# CPU.net
KiCad netlist of a schematic drawn in Altium Designer
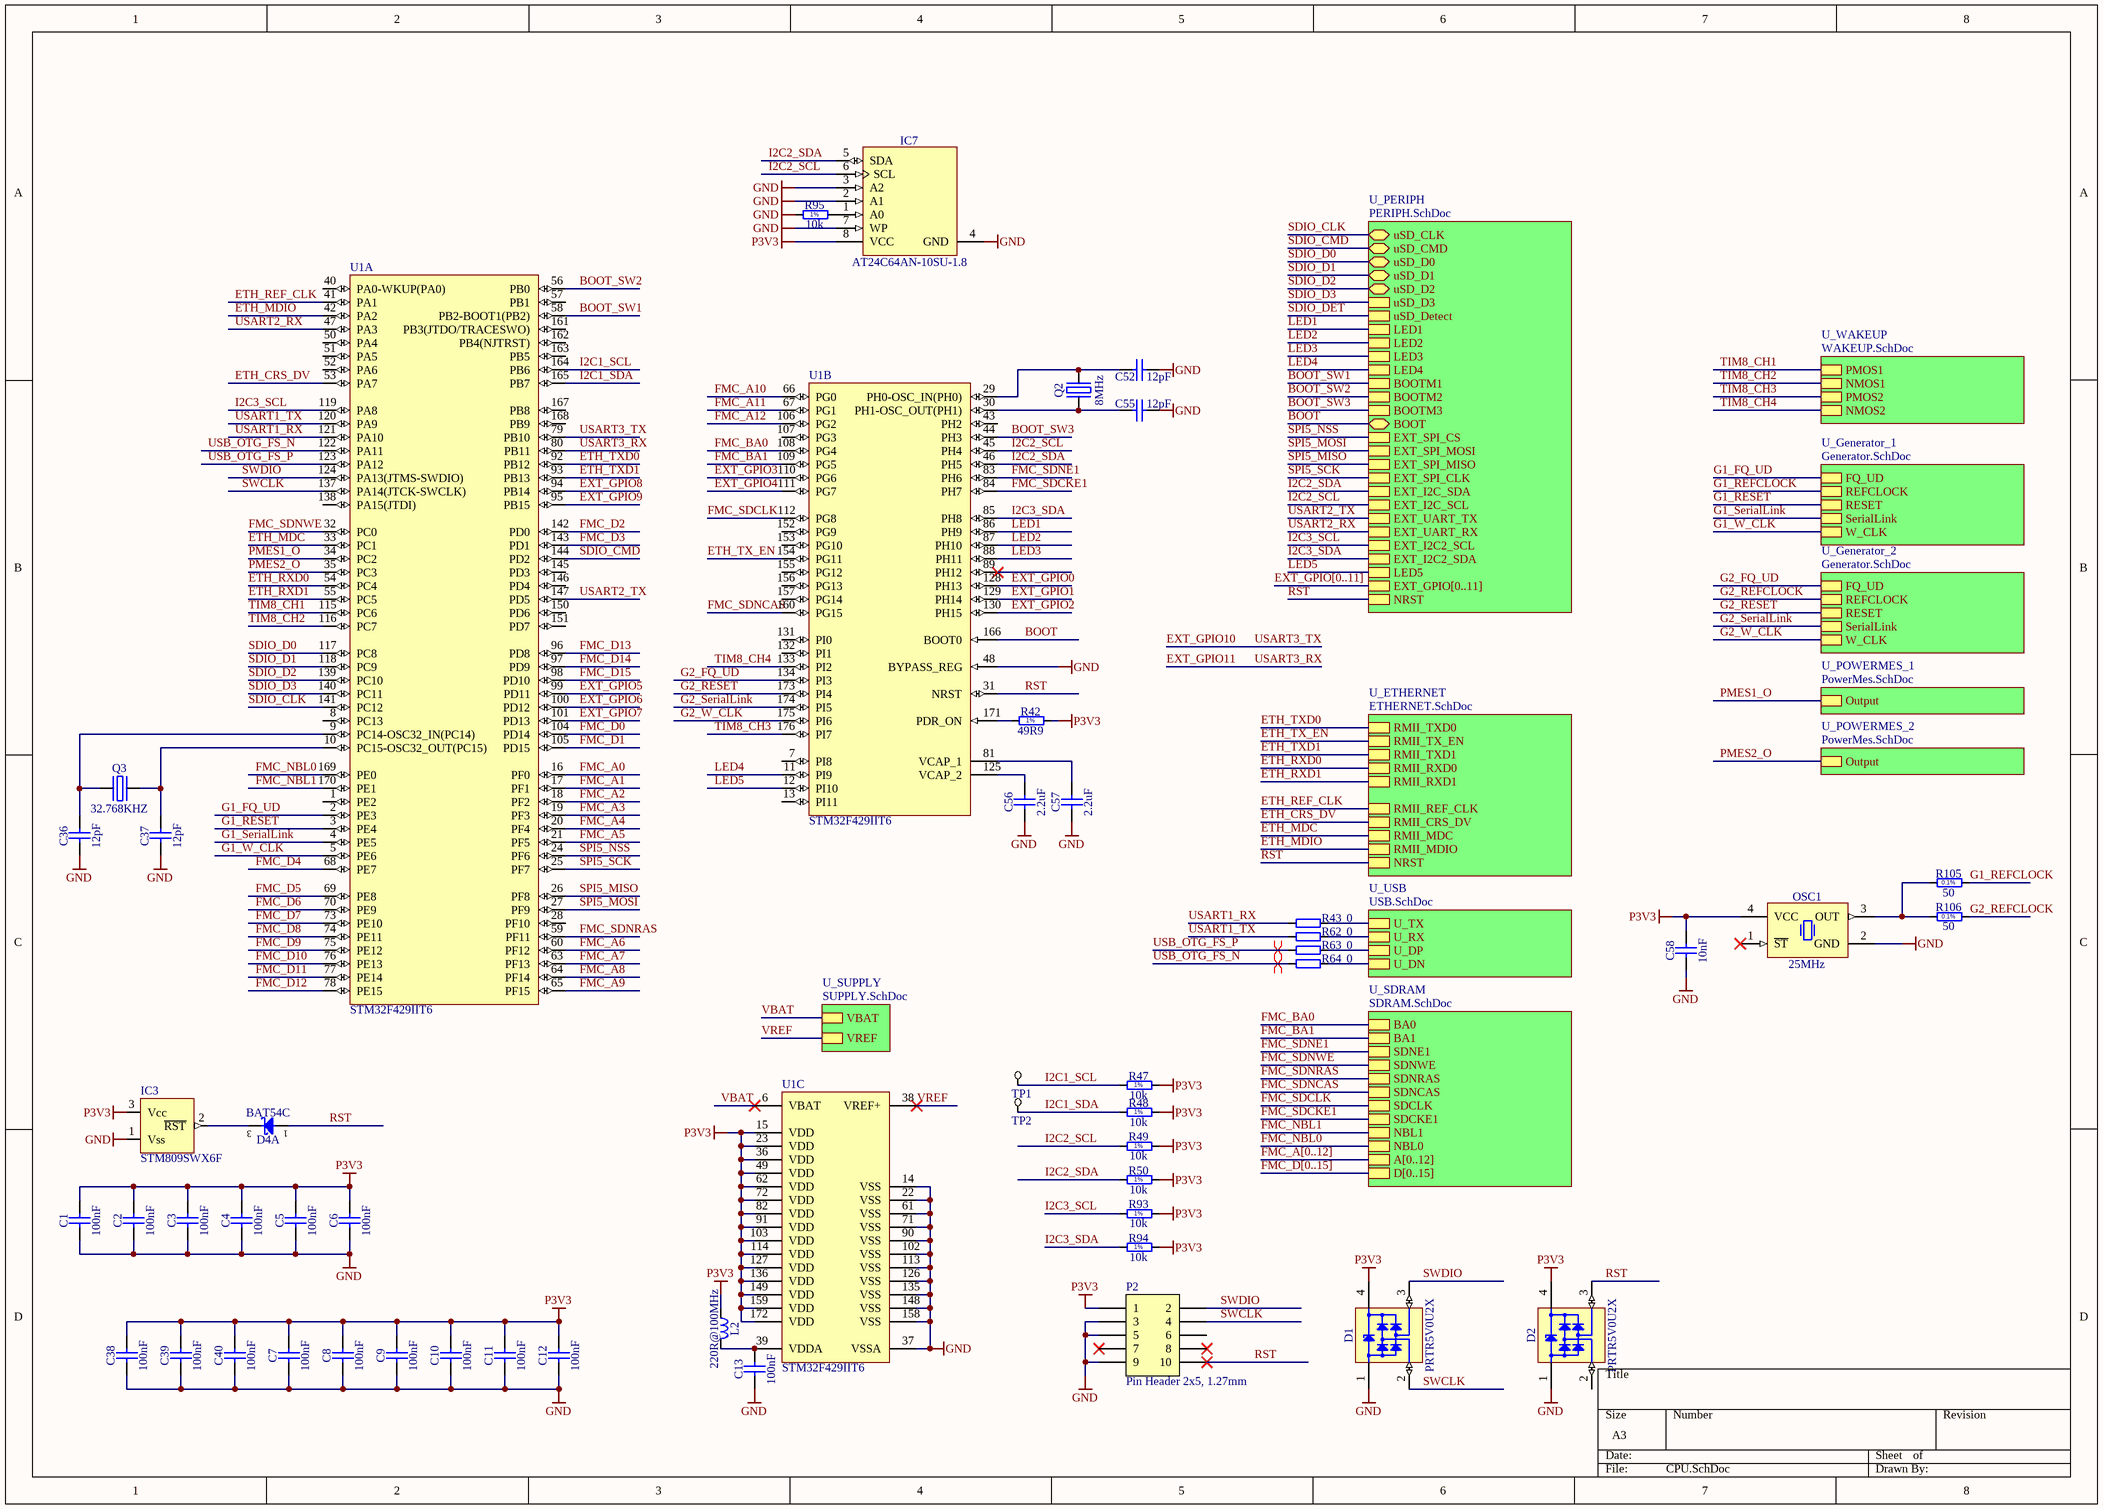
[diagram p0: CPU.SchDoc]

(export (version "E")
  (design (tool "Eeschema 10.0.6"))
  (components
    (comp (ref "C1")
      (value "100nF")
      (footprint "CAPC1005X55N")
      (description "Non-polarised capacitor")
      (fields
        (field (name "PART NUMBER") "CC0402_100NF_16V_10%_X5R")
        (field (name "VOLTAGE") "16V")
        (field (name "AUTHOR") "CERN DEM JLC")
      )
      (libsource (lib "Capacitors") (part "Capacitor - non polarized"))
    )
    (comp (ref "C2")
      (value "100nF")
      (footprint "CAPC1005X55N")
      (description "Non-polarised capacitor")
      (fields
        (field (name "PART NUMBER") "CC0402_100NF_16V_10%_X5R")
        (field (name "VOLTAGE") "16V")
        (field (name "AUTHOR") "CERN DEM JLC")
      )
      (libsource (lib "Capacitors") (part "Capacitor - non polarized"))
    )
    (comp (ref "C3")
      (value "100nF")
      (footprint "CAPC1005X55N")
      (description "Non-polarised capacitor")
      (fields
        (field (name "PART NUMBER") "CC0402_100NF_16V_10%_X5R")
        (field (name "VOLTAGE") "16V")
        (field (name "AUTHOR") "CERN DEM JLC")
      )
      (libsource (lib "Capacitors") (part "Capacitor - non polarized"))
    )
    (comp (ref "C4")
      (value "100nF")
      (footprint "CAPC1005X55N")
      (description "Non-polarised capacitor")
      (fields
        (field (name "PART NUMBER") "CC0402_100NF_16V_10%_X5R")
        (field (name "VOLTAGE") "16V")
        (field (name "AUTHOR") "CERN DEM JLC")
      )
      (libsource (lib "Capacitors") (part "Capacitor - non polarized"))
    )
    (comp (ref "C5")
      (value "100nF")
      (footprint "CAPC1005X55N")
      (description "Non-polarised capacitor")
      (fields
        (field (name "PART NUMBER") "CC0402_100NF_16V_10%_X5R")
        (field (name "VOLTAGE") "16V")
        (field (name "AUTHOR") "CERN DEM JLC")
      )
      (libsource (lib "Capacitors") (part "Capacitor - non polarized"))
    )
    (comp (ref "C6")
      (value "100nF")
      (footprint "CAPC1005X55N")
      (description "Non-polarised capacitor")
      (fields
        (field (name "PART NUMBER") "CC0402_100NF_16V_10%_X5R")
        (field (name "VOLTAGE") "16V")
        (field (name "AUTHOR") "CERN DEM JLC")
      )
      (libsource (lib "Capacitors") (part "Capacitor - non polarized"))
    )
    (comp (ref "C7")
      (value "100nF")
      (footprint "CAPC1005X55N")
      (description "Non-polarised capacitor")
      (fields
        (field (name "PART NUMBER") "CC0402_100NF_16V_10%_X5R")
        (field (name "VOLTAGE") "16V")
        (field (name "AUTHOR") "CERN DEM JLC")
      )
      (libsource (lib "Capacitors") (part "Capacitor - non polarized"))
    )
    (comp (ref "C8")
      (value "100nF")
      (footprint "CAPC1005X55N")
      (description "Non-polarised capacitor")
      (fields
        (field (name "PART NUMBER") "CC0402_100NF_16V_10%_X5R")
        (field (name "VOLTAGE") "16V")
        (field (name "AUTHOR") "CERN DEM JLC")
      )
      (libsource (lib "Capacitors") (part "Capacitor - non polarized"))
    )
    (comp (ref "C9")
      (value "100nF")
      (footprint "CAPC1005X55N")
      (description "Non-polarised capacitor")
      (fields
        (field (name "PART NUMBER") "CC0402_100NF_16V_10%_X5R")
        (field (name "VOLTAGE") "16V")
        (field (name "AUTHOR") "CERN DEM JLC")
      )
      (libsource (lib "Capacitors") (part "Capacitor - non polarized"))
    )
    (comp (ref "C10")
      (value "100nF")
      (footprint "CAPC1005X55N")
      (description "Non-polarised capacitor")
      (fields
        (field (name "PART NUMBER") "CC0402_100NF_16V_10%_X5R")
        (field (name "VOLTAGE") "16V")
        (field (name "AUTHOR") "CERN DEM JLC")
      )
      (libsource (lib "Capacitors") (part "Capacitor - non polarized"))
    )
    (comp (ref "C11")
      (value "100nF")
      (footprint "CAPC1005X55N")
      (description "Non-polarised capacitor")
      (fields
        (field (name "PART NUMBER") "CC0402_100NF_16V_10%_X5R")
        (field (name "VOLTAGE") "16V")
        (field (name "AUTHOR") "CERN DEM JLC")
      )
      (libsource (lib "Capacitors") (part "Capacitor - non polarized"))
    )
    (comp (ref "C12")
      (value "100nF")
      (footprint "CAPC1005X55N")
      (description "Non-polarised capacitor")
      (fields
        (field (name "PART NUMBER") "CC0402_100NF_16V_10%_X5R")
        (field (name "VOLTAGE") "16V")
        (field (name "AUTHOR") "CERN DEM JLC")
      )
      (libsource (lib "Capacitors") (part "Capacitor - non polarized"))
    )
    (comp (ref "C13")
      (value "100nF")
      (footprint "CAPC1005X55N")
      (description "Non-polarised capacitor")
      (fields
        (field (name "PART NUMBER") "CC0402_100NF_16V_10%_X5R")
        (field (name "VOLTAGE") "16V")
        (field (name "AUTHOR") "CERN DEM JLC")
      )
      (libsource (lib "Capacitors") (part "Capacitor - non polarized"))
    )
    (comp (ref "C36")
      (value "12pF")
      (footprint "CAPC1005X55N")
      (description "Non-polarised capacitor")
      (fields
        (field (name "PART NUMBER") "CC0402_12PF_50V_5%_C0G")
        (field (name "VOLTAGE") "50V")
        (field (name "AUTHOR") "CERN DEM JLC")
      )
      (libsource (lib "Capacitors") (part "Capacitor - non polarized"))
    )
    (comp (ref "C37")
      (value "12pF")
      (footprint "CAPC1005X55N")
      (description "Non-polarised capacitor")
      (fields
        (field (name "PART NUMBER") "CC0402_12PF_50V_5%_C0G")
        (field (name "VOLTAGE") "50V")
        (field (name "AUTHOR") "CERN DEM JLC")
      )
      (libsource (lib "Capacitors") (part "Capacitor - non polarized"))
    )
    (comp (ref "C38")
      (value "100nF")
      (footprint "CAPC1005X55N")
      (description "Non-polarised capacitor")
      (fields
        (field (name "PART NUMBER") "CC0402_100NF_16V_10%_X5R")
        (field (name "VOLTAGE") "16V")
        (field (name "AUTHOR") "CERN DEM JLC")
      )
      (libsource (lib "Capacitors") (part "Capacitor - non polarized"))
    )
    (comp (ref "C39")
      (value "100nF")
      (footprint "CAPC1005X55N")
      (description "Non-polarised capacitor")
      (fields
        (field (name "PART NUMBER") "CC0402_100NF_16V_10%_X5R")
        (field (name "VOLTAGE") "16V")
        (field (name "AUTHOR") "CERN DEM JLC")
      )
      (libsource (lib "Capacitors") (part "Capacitor - non polarized"))
    )
    (comp (ref "C40")
      (value "100nF")
      (footprint "CAPC1005X55N")
      (description "Non-polarised capacitor")
      (fields
        (field (name "PART NUMBER") "CC0402_100NF_16V_10%_X5R")
        (field (name "VOLTAGE") "16V")
        (field (name "AUTHOR") "CERN DEM JLC")
      )
      (libsource (lib "Capacitors") (part "Capacitor - non polarized"))
    )
    (comp (ref "C52")
      (value "12pF")
      (footprint "CAPC1005X55N")
      (description "Non-polarised capacitor")
      (fields
        (field (name "PART NUMBER") "CC0402_12PF_50V_5%_C0G")
        (field (name "VOLTAGE") "50V")
        (field (name "AUTHOR") "CERN DEM JLC")
      )
      (libsource (lib "Capacitors") (part "Capacitor - non polarized"))
    )
    (comp (ref "C55")
      (value "12pF")
      (footprint "CAPC1005X55N")
      (description "Non-polarised capacitor")
      (fields
        (field (name "PART NUMBER") "CC0402_12PF_50V_5%_C0G")
        (field (name "VOLTAGE") "50V")
        (field (name "AUTHOR") "CERN DEM JLC")
      )
      (libsource (lib "Capacitors") (part "Capacitor - non polarized"))
    )
    (comp (ref "C56")
      (value "2.2uF")
      (footprint "CAPC1608X87N")
      (description "Non-polarised capacitor")
      (fields
        (field (name "PART NUMBER") "CC0603_2.2UF_16V_10%_X5R")
        (field (name "VOLTAGE") "16V")
        (field (name "AUTHOR") "CERN DEM JLC")
      )
      (libsource (lib "Capacitors") (part "Capacitor - non polarized"))
    )
    (comp (ref "C57")
      (value "2.2uF")
      (footprint "CAPC1608X87N")
      (description "Non-polarised capacitor")
      (fields
        (field (name "PART NUMBER") "CC0603_2.2UF_16V_10%_X5R")
        (field (name "VOLTAGE") "16V")
        (field (name "AUTHOR") "CERN DEM JLC")
      )
      (libsource (lib "Capacitors") (part "Capacitor - non polarized"))
    )
    (comp (ref "C58")
      (value "10nF")
      (footprint "CAPC1005X55N")
      (description "Non-polarised capacitor")
      (fields
        (field (name "PART NUMBER") "CC0402_10NF_16V_10%_X7R")
        (field (name "VOLTAGE") "16V")
        (field (name "AUTHOR") "CERN DEM JLC")
      )
      (libsource (lib "Capacitors") (part "Capacitor - non polarized"))
    )
    (comp (ref "D1")
      (value "PRTR5V0U2X")
      (footprint "SOT190P230X110-4N")
      (description "Ultra Low Capacitance Double Rail-to-Rail ESD Protection Diode")
      (fields
        (field (name "VOLTAGE") "5.5V")
        (field (name "MANUFACTURER") "NXP SEMICONDUCTORS")
        (field (name "AUTHOR") "CERN DEM JLC")
      )
      (libsource (lib "ICs And Semiconductors") (part "PRTR5V0U2X"))
    )
    (comp (ref "D2")
      (value "PRTR5V0U2X")
      (footprint "SOT190P230X110-4N")
      (description "Ultra Low Capacitance Double Rail-to-Rail ESD Protection Diode")
      (fields
        (field (name "VOLTAGE") "5.5V")
        (field (name "MANUFACTURER") "NXP SEMICONDUCTORS")
        (field (name "AUTHOR") "CERN DEM JLC")
      )
      (libsource (lib "ICs And Semiconductors") (part "PRTR5V0U2X"))
    )
    (comp (ref "D4")
      (value "BAT54C")
      (footprint "SOT95P240X130-3N")
      (description "Dual Common Cathode Schottky Diodes")
      (fields
        (field (name "VOLTAGE") "30V")
        (field (name "POWER") "200mA")
        (field (name "AUTHOR") "CERN DEM JLC")
      )
      (libsource (lib "ICs And Semiconductors") (part "Diode Schottky x2 A1C3_A2C3"))
    )
    (comp (ref "IC3")
      (value "STM809SWX6F")
      (footprint "SOT95P229X119-3N")
      (description "2.93V  Reset circuit")
      (libsource (lib "LIBRARY_SCH") (part "VMON_STM809"))
    )
    (comp (ref "IC7")
      (value "AT24C64AN-10SU-1.8")
      (footprint "SOIC127P600X175-8N")
      (description "64K (8192 x 8), Two-Wire Serial EEPROM")
      (fields (field (name "MANUFACTURER") "ATMEL") (field (name "AUTHOR") "CERN DEM JLC"))
      (libsource (lib "ICs And Semiconductors") (part "AT24C64AN-10SU"))
    )
    (comp (ref "L2")
      (value "220R@100MHz")
      (footprint "INDC2012X105N")
      (description "Inductor")
      (fields
        (field (name "PART NUMBER") "IND0805_MURATA_BLM21PG221SN1D")
        (field (name "POWER") "2A")
        (field (name "AUTHOR") "CERN DEM JLC")
      )
      (libsource (lib "Inductors & Transformers") (part "Inductor"))
    )
    (comp (ref "OSC1")
      (value "25MHz")
      (footprint "OSC_MICREL_2520")
      (description "Oscillator 4 pins 1=\\ST 2=GND 3=OUT 4=VCC")
      (fields
        (field (name "PART NUMBER") "OSC_25MHZ_MICREL_DSC1001DI5-025.0000T")
        (field (name "MANUFACTURER") "MICREL")
        (field (name "AUTHOR") "CERN DEM JLC")
      )
      (libsource (lib "ICs And Semiconductors") (part "Oscillator 1ST 2GND 3OUT 4VCC"))
    )
    (comp (ref "P2")
      (value "Pin Header 2x5, 1.27mm")
      (footprint "HDR_2x5-SMD-1.27mm-K")
      (description "Pin Header 2x5, 1.27mm (50mil), SMD, Keying Shroud")
      (fields
        (field (name "PART NUMBER") "Pin Header 2x5 SMD, 1.27mm, KS")
        (field (name "MANUFACTURER") "WCON")
        (field (name "PUBLISHER") "Nordic Semiconductor")
      )
      (libsource (lib "Nordic Passive DB") (part "CONN-2x5"))
    )
    (comp (ref "Q2")
      (value "8MHz")
      (footprint "XTAL_TXC_7A")
      (description "Quartz Crystal")
      (fields
        (field (name "PART NUMBER") "XTAL_8MHZ_TXC_7A-8.000MAAE-T")
        (field (name "MANUFACTURER") "TXC CORPORATION")
        (field (name "AUTHOR") "CERN DEM JLC")
      )
      (libsource (lib "ICs And Semiconductors") (part "Quartz Crystal"))
    )
    (comp (ref "Q3")
      (value "32.768KHZ")
      (footprint "XTAL_ABRACON_ABS09")
      (description "Quartz Crystal")
      (fields
        (field (name "PART NUMBER") "XTAL_32.768KHZ_ABRACON_ABS09-32.768KHZ-T")
        (field (name "MANUFACTURER") "ABRACON")
        (field (name "AUTHOR") "CERN DEM JLC")
      )
      (libsource (lib "ICs And Semiconductors") (part "Quartz Crystal"))
    )
    (comp (ref "R42")
      (value "49R9")
      (footprint "RESC1005X40N")
      (description "Resistor - 1%")
      (fields
        (field (name "PART NUMBER") "R0402_49R9_1%_0.0625W_100PPM")
        (field (name "POWER") "0.0625W")
        (field (name "AUTHOR") "CERN DEM JLC")
      )
      (libsource (lib "Resistors") (part "Resistor - 1%"))
    )
    (comp (ref "R43")
      (value "0")
      (footprint "RESC1005X40N")
      (description "Resistor")
      (fields
        (field (name "PART NUMBER") "R0402_0R_JUMPER")
        (field (name "MANUFACTURER") "GENERIC")
        (field (name "AUTHOR") "CERN DEM JLC")
      )
      (libsource (lib "Resistors") (part "Resistor"))
    )
    (comp (ref "R47")
      (value "10k")
      (footprint "RESC1005X40N")
      (description "Resistor - 1%")
      (fields
        (field (name "PART NUMBER") "R0402_10K_1%_0.0625W_100PPM")
        (field (name "POWER") "0.0625W")
        (field (name "AUTHOR") "CERN DEM JLC")
      )
      (libsource (lib "Resistors") (part "Resistor - 1%"))
    )
    (comp (ref "R48")
      (value "10k")
      (footprint "RESC1005X40N")
      (description "Resistor - 1%")
      (fields
        (field (name "PART NUMBER") "R0402_10K_1%_0.0625W_100PPM")
        (field (name "POWER") "0.0625W")
        (field (name "AUTHOR") "CERN DEM JLC")
      )
      (libsource (lib "Resistors") (part "Resistor - 1%"))
    )
    (comp (ref "R49")
      (value "10k")
      (footprint "RESC1005X40N")
      (description "Resistor - 1%")
      (fields
        (field (name "PART NUMBER") "R0402_10K_1%_0.0625W_100PPM")
        (field (name "POWER") "0.0625W")
        (field (name "AUTHOR") "CERN DEM JLC")
      )
      (libsource (lib "Resistors") (part "Resistor - 1%"))
    )
    (comp (ref "R50")
      (value "10k")
      (footprint "RESC1005X40N")
      (description "Resistor - 1%")
      (fields
        (field (name "PART NUMBER") "R0402_10K_1%_0.0625W_100PPM")
        (field (name "POWER") "0.0625W")
        (field (name "AUTHOR") "CERN DEM JLC")
      )
      (libsource (lib "Resistors") (part "Resistor - 1%"))
    )
    (comp (ref "R62")
      (value "0")
      (footprint "RESC1005X40N")
      (description "Resistor")
      (fields
        (field (name "PART NUMBER") "R0402_0R_JUMPER")
        (field (name "MANUFACTURER") "GENERIC")
        (field (name "AUTHOR") "CERN DEM JLC")
      )
      (libsource (lib "Resistors") (part "Resistor"))
    )
    (comp (ref "R63")
      (value "0")
      (footprint "RESC1005X40N")
      (description "Resistor")
      (fields
        (field (name "PART NUMBER") "R0402_0R_JUMPER")
        (field (name "MANUFACTURER") "GENERIC")
        (field (name "AUTHOR") "CERN DEM JLC")
      )
      (libsource (lib "Resistors") (part "Resistor"))
    )
    (comp (ref "R64")
      (value "0")
      (footprint "RESC1005X40N")
      (description "Resistor")
      (fields
        (field (name "PART NUMBER") "R0402_0R_JUMPER")
        (field (name "MANUFACTURER") "GENERIC")
        (field (name "AUTHOR") "CERN DEM JLC")
      )
      (libsource (lib "Resistors") (part "Resistor"))
    )
    (comp (ref "R93")
      (value "10k")
      (footprint "RESC1005X40N")
      (description "Resistor - 1%")
      (fields
        (field (name "PART NUMBER") "R0402_10K_1%_0.0625W_100PPM")
        (field (name "POWER") "0.0625W")
        (field (name "AUTHOR") "CERN DEM JLC")
      )
      (libsource (lib "Resistors") (part "Resistor - 1%"))
    )
    (comp (ref "R94")
      (value "10k")
      (footprint "RESC1005X40N")
      (description "Resistor - 1%")
      (fields
        (field (name "PART NUMBER") "R0402_10K_1%_0.0625W_100PPM")
        (field (name "POWER") "0.0625W")
        (field (name "AUTHOR") "CERN DEM JLC")
      )
      (libsource (lib "Resistors") (part "Resistor - 1%"))
    )
    (comp (ref "R95")
      (value "10k")
      (footprint "RESC1005X40N")
      (description "Resistor - 1%")
      (fields
        (field (name "PART NUMBER") "R0402_10K_1%_0.0625W_100PPM")
        (field (name "POWER") "0.0625W")
        (field (name "AUTHOR") "CERN DEM JLC")
      )
      (libsource (lib "Resistors") (part "Resistor - 1%"))
    )
    (comp (ref "R105")
      (value "50")
      (footprint "RESC1005X35N")
      (description "Resistor - 0.1%")
      (fields
        (field (name "PART NUMBER") "R0402_50R_0.1%_0.05W_25PPM")
        (field (name "POWER") "0.05W")
        (field (name "AUTHOR") "CERN DEM JMW")
      )
      (libsource (lib "Resistors") (part "Resistor - 0.1%"))
    )
    (comp (ref "R106")
      (value "50")
      (footprint "RESC1005X35N")
      (description "Resistor - 0.1%")
      (fields
        (field (name "PART NUMBER") "R0402_50R_0.1%_0.05W_25PPM")
        (field (name "POWER") "0.05W")
        (field (name "AUTHOR") "CERN DEM JMW")
      )
      (libsource (lib "Resistors") (part "Resistor - 0.1%"))
    )
    (comp (ref "TP1")
      (value "TP")
      (footprint "TP")
      (description "Testpoint")
      (libsource (lib "Charger_base_station v2.2") (part "TP"))
    )
    (comp (ref "TP2")
      (value "TP")
      (footprint "TP")
      (description "Testpoint")
      (libsource (lib "Charger_base_station v2.2") (part "TP"))
    )
    (comp (ref "U1")
      (value "STM32F429IIT6")
      (footprint "STM-LQFP176_N")
      (fields (field (name "MANUFACTURER") "STMicroelectronics"))
      (libsource (lib "STMicroelectronics STM32 F4") (part "STM32F429IIT6"))
    )
  )
  (nets
    (net (code "1") (name "/BOOT") (class "Default")
      (node (ref "U1") (pin "166") (pinfunction "BOOT0_166") (pintype "input"))
    )
    (net (code "2") (name "/BOOT_SW1") (class "Default")
      (node (ref "U1") (pin "58") (pinfunction "PB2-BOOT1(PB2)_58") (pintype "bidirectional"))
    )
    (net (code "3") (name "/BOOT_SW2") (class "Default")
      (node (ref "U1") (pin "56") (pinfunction "PB0_56") (pintype "bidirectional"))
    )
    (net (code "4") (name "/BOOT_SW3") (class "Default")
      (node (ref "U1") (pin "44") (pinfunction "PH3_44") (pintype "bidirectional"))
    )
    (net (code "5") (name "/ETH_CRS_DV") (class "Default")
      (node (ref "U1") (pin "53") (pinfunction "PA7_53") (pintype "bidirectional"))
    )
    (net (code "6") (name "/ETH_MDC") (class "Default")
      (node (ref "U1") (pin "33") (pinfunction "PC1_33") (pintype "bidirectional"))
    )
    (net (code "7") (name "/ETH_MDIO") (class "Default")
      (node (ref "U1") (pin "42") (pinfunction "PA2_42") (pintype "bidirectional"))
    )
    (net (code "8") (name "/ETH_REF_CLK") (class "Default")
      (node (ref "U1") (pin "41") (pinfunction "PA1_41") (pintype "bidirectional"))
    )
    (net (code "9") (name "/ETH_RXD0") (class "Default")
      (node (ref "U1") (pin "54") (pinfunction "PC4_54") (pintype "bidirectional"))
    )
    (net (code "10") (name "/ETH_RXD1") (class "Default")
      (node (ref "U1") (pin "55") (pinfunction "PC5_55") (pintype "bidirectional"))
    )
    (net (code "11") (name "/ETH_TXD0") (class "Default")
      (node (ref "U1") (pin "92") (pinfunction "PB12_92") (pintype "bidirectional"))
    )
    (net (code "12") (name "/ETH_TXD1") (class "Default")
      (node (ref "U1") (pin "93") (pinfunction "PB13_93") (pintype "bidirectional"))
    )
    (net (code "13") (name "/ETH_TX_EN") (class "Default")
      (node (ref "U1") (pin "154") (pinfunction "PG11_154") (pintype "bidirectional"))
    )
    (net (code "14") (name "/EXT_GPIO0") (class "Default")
      (node (ref "U1") (pin "128") (pinfunction "PH13_128") (pintype "bidirectional"))
    )
    (net (code "15") (name "/EXT_GPIO1") (class "Default")
      (node (ref "U1") (pin "129") (pinfunction "PH14_129") (pintype "bidirectional"))
    )
    (net (code "16") (name "/EXT_GPIO2") (class "Default")
      (node (ref "U1") (pin "130") (pinfunction "PH15_130") (pintype "bidirectional"))
    )
    (net (code "17") (name "/EXT_GPIO3") (class "Default")
      (node (ref "U1") (pin "110") (pinfunction "PG6_110") (pintype "bidirectional"))
    )
    (net (code "18") (name "/EXT_GPIO4") (class "Default")
      (node (ref "U1") (pin "111") (pinfunction "PG7_111") (pintype "bidirectional"))
    )
    (net (code "19") (name "/EXT_GPIO5") (class "Default")
      (node (ref "U1") (pin "99") (pinfunction "PD11_99") (pintype "bidirectional"))
    )
    (net (code "20") (name "/EXT_GPIO6") (class "Default")
      (node (ref "U1") (pin "100") (pinfunction "PD12_100") (pintype "bidirectional"))
    )
    (net (code "21") (name "/EXT_GPIO7") (class "Default")
      (node (ref "U1") (pin "101") (pinfunction "PD13_101") (pintype "bidirectional"))
    )
    (net (code "22") (name "/EXT_GPIO8") (class "Default")
      (node (ref "U1") (pin "94") (pinfunction "PB14_94") (pintype "bidirectional"))
    )
    (net (code "23") (name "/EXT_GPIO9") (class "Default")
      (node (ref "U1") (pin "95") (pinfunction "PB15_95") (pintype "bidirectional"))
    )
    (net (code "24") (name "/EXT_GPIO10") (class "Default")
      (node (ref "U1") (pin "79") (pinfunction "PB10_79") (pintype "bidirectional"))
    )
    (net (code "25") (name "/EXT_GPIO11") (class "Default")
      (node (ref "U1") (pin "80") (pinfunction "PB11_80") (pintype "bidirectional"))
    )
    (net (code "27") (name "/FMC_A0") (class "Default")
      (node (ref "U1") (pin "16") (pinfunction "PF0_16") (pintype "bidirectional"))
    )
    (net (code "28") (name "/FMC_A1") (class "Default")
      (node (ref "U1") (pin "17") (pinfunction "PF1_17") (pintype "bidirectional"))
    )
    (net (code "29") (name "/FMC_A2") (class "Default")
      (node (ref "U1") (pin "18") (pinfunction "PF2_18") (pintype "bidirectional"))
    )
    (net (code "30") (name "/FMC_A3") (class "Default")
      (node (ref "U1") (pin "19") (pinfunction "PF3_19") (pintype "bidirectional"))
    )
    (net (code "31") (name "/FMC_A4") (class "Default")
      (node (ref "U1") (pin "20") (pinfunction "PF4_20") (pintype "bidirectional"))
    )
    (net (code "32") (name "/FMC_A5") (class "Default")
      (node (ref "U1") (pin "21") (pinfunction "PF5_21") (pintype "bidirectional"))
    )
    (net (code "33") (name "/FMC_A6") (class "Default")
      (node (ref "U1") (pin "60") (pinfunction "PF12_60") (pintype "bidirectional"))
    )
    (net (code "34") (name "/FMC_A7") (class "Default")
      (node (ref "U1") (pin "63") (pinfunction "PF13_63") (pintype "bidirectional"))
    )
    (net (code "35") (name "/FMC_A8") (class "Default")
      (node (ref "U1") (pin "64") (pinfunction "PF14_64") (pintype "bidirectional"))
    )
    (net (code "36") (name "/FMC_A9") (class "Default")
      (node (ref "U1") (pin "65") (pinfunction "PF15_65") (pintype "bidirectional"))
    )
    (net (code "37") (name "/FMC_A10") (class "Default")
      (node (ref "U1") (pin "66") (pinfunction "PG0_66") (pintype "bidirectional"))
    )
    (net (code "38") (name "/FMC_A11") (class "Default")
      (node (ref "U1") (pin "67") (pinfunction "PG1_67") (pintype "bidirectional"))
    )
    (net (code "39") (name "/FMC_A12") (class "Default")
      (node (ref "U1") (pin "106") (pinfunction "PG2_106") (pintype "bidirectional"))
    )
    (net (code "41") (name "/FMC_BA0") (class "Default")
      (node (ref "U1") (pin "108") (pinfunction "PG4_108") (pintype "bidirectional"))
    )
    (net (code "42") (name "/FMC_BA1") (class "Default")
      (node (ref "U1") (pin "109") (pinfunction "PG5_109") (pintype "bidirectional"))
    )
    (net (code "43") (name "/FMC_D0") (class "Default")
      (node (ref "U1") (pin "104") (pinfunction "PD14_104") (pintype "bidirectional"))
    )
    (net (code "44") (name "/FMC_D1") (class "Default")
      (node (ref "U1") (pin "105") (pinfunction "PD15_105") (pintype "bidirectional"))
    )
    (net (code "45") (name "/FMC_D2") (class "Default")
      (node (ref "U1") (pin "142") (pinfunction "PD0_142") (pintype "bidirectional"))
    )
    (net (code "46") (name "/FMC_D3") (class "Default")
      (node (ref "U1") (pin "143") (pinfunction "PD1_143") (pintype "bidirectional"))
    )
    (net (code "47") (name "/FMC_D4") (class "Default")
      (node (ref "U1") (pin "68") (pinfunction "PE7_68") (pintype "bidirectional"))
    )
    (net (code "48") (name "/FMC_D5") (class "Default")
      (node (ref "U1") (pin "69") (pinfunction "PE8_69") (pintype "bidirectional"))
    )
    (net (code "49") (name "/FMC_D6") (class "Default")
      (node (ref "U1") (pin "70") (pinfunction "PE9_70") (pintype "bidirectional"))
    )
    (net (code "50") (name "/FMC_D7") (class "Default")
      (node (ref "U1") (pin "73") (pinfunction "PE10_73") (pintype "bidirectional"))
    )
    (net (code "51") (name "/FMC_D8") (class "Default")
      (node (ref "U1") (pin "74") (pinfunction "PE11_74") (pintype "bidirectional"))
    )
    (net (code "52") (name "/FMC_D9") (class "Default")
      (node (ref "U1") (pin "75") (pinfunction "PE12_75") (pintype "bidirectional"))
    )
    (net (code "53") (name "/FMC_D10") (class "Default")
      (node (ref "U1") (pin "76") (pinfunction "PE13_76") (pintype "bidirectional"))
    )
    (net (code "54") (name "/FMC_D11") (class "Default")
      (node (ref "U1") (pin "77") (pinfunction "PE14_77") (pintype "bidirectional"))
    )
    (net (code "55") (name "/FMC_D12") (class "Default")
      (node (ref "U1") (pin "78") (pinfunction "PE15_78") (pintype "bidirectional"))
    )
    (net (code "56") (name "/FMC_D13") (class "Default")
      (node (ref "U1") (pin "96") (pinfunction "PD8_96") (pintype "bidirectional"))
    )
    (net (code "57") (name "/FMC_D14") (class "Default")
      (node (ref "U1") (pin "97") (pinfunction "PD9_97") (pintype "bidirectional"))
    )
    (net (code "58") (name "/FMC_D15") (class "Default")
      (node (ref "U1") (pin "98") (pinfunction "PD10_98") (pintype "bidirectional"))
    )
    (net (code "60") (name "/FMC_NBL0") (class "Default")
      (node (ref "U1") (pin "169") (pinfunction "PE0_169") (pintype "bidirectional"))
    )
    (net (code "61") (name "/FMC_NBL1") (class "Default")
      (node (ref "U1") (pin "170") (pinfunction "PE1_170") (pintype "bidirectional"))
    )
    (net (code "62") (name "/FMC_SDCKE1") (class "Default")
      (node (ref "U1") (pin "84") (pinfunction "PH7_84") (pintype "bidirectional"))
    )
    (net (code "63") (name "/FMC_SDCLK") (class "Default")
      (node (ref "U1") (pin "112") (pinfunction "PG8_112") (pintype "bidirectional"))
    )
    (net (code "64") (name "/FMC_SDNCAS") (class "Default")
      (node (ref "U1") (pin "160") (pinfunction "PG15_160") (pintype "bidirectional"))
    )
    (net (code "65") (name "/FMC_SDNE1") (class "Default")
      (node (ref "U1") (pin "83") (pinfunction "PH6_83") (pintype "bidirectional"))
    )
    (net (code "66") (name "/FMC_SDNRAS") (class "Default")
      (node (ref "U1") (pin "59") (pinfunction "PF11_59") (pintype "bidirectional"))
    )
    (net (code "67") (name "/FMC_SDNWE") (class "Default")
      (node (ref "U1") (pin "32") (pinfunction "PC0_32") (pintype "bidirectional"))
    )
    (net (code "68") (name "/G1_FQ_UD") (class "Default")
      (node (ref "U1") (pin "2") (pinfunction "PE3_2") (pintype "bidirectional"))
    )
    (net (code "69") (name "/G1_REFCLOCK") (class "Default")
      (node (ref "R105") (pin "2") (pinfunction "2_2") (pintype "passive"))
    )
    (net (code "70") (name "/G1_RESET") (class "Default")
      (node (ref "U1") (pin "3") (pinfunction "PE4_3") (pintype "bidirectional"))
    )
    (net (code "71") (name "/G1_SerialLink") (class "Default")
      (node (ref "U1") (pin "4") (pinfunction "PE5_4") (pintype "bidirectional"))
    )
    (net (code "72") (name "/G1_W_CLK") (class "Default")
      (node (ref "U1") (pin "5") (pinfunction "PE6_5") (pintype "bidirectional"))
    )
    (net (code "73") (name "/G2_FQ_UD") (class "Default")
      (node (ref "U1") (pin "134") (pinfunction "PI3_134") (pintype "bidirectional"))
    )
    (net (code "74") (name "/G2_REFCLOCK") (class "Default")
      (node (ref "R106") (pin "2") (pinfunction "2_2") (pintype "passive"))
    )
    (net (code "75") (name "/G2_RESET") (class "Default")
      (node (ref "U1") (pin "173") (pinfunction "PI4_173") (pintype "bidirectional"))
    )
    (net (code "76") (name "/G2_SerialLink") (class "Default")
      (node (ref "U1") (pin "174") (pinfunction "PI5_174") (pintype "bidirectional"))
    )
    (net (code "77") (name "/G2_W_CLK") (class "Default")
      (node (ref "U1") (pin "175") (pinfunction "PI6_175") (pintype "bidirectional"))
    )
    (net (code "78") (name "/I2C1_SCL") (class "Default")
      (node (ref "R47") (pin "1") (pinfunction "1_1") (pintype "passive"))
      (node (ref "TP1") (pin "1") (pintype "passive"))
      (node (ref "U1") (pin "164") (pinfunction "PB6_164") (pintype "bidirectional"))
    )
    (net (code "79") (name "/I2C1_SDA") (class "Default")
      (node (ref "R48") (pin "1") (pinfunction "1_1") (pintype "passive"))
      (node (ref "TP2") (pin "1") (pintype "passive"))
      (node (ref "U1") (pin "165") (pinfunction "PB7_165") (pintype "bidirectional"))
    )
    (net (code "80") (name "/I2C2_SCL") (class "Default")
      (node (ref "IC7") (pin "6") (pinfunction "SCL_6") (pintype "input"))
      (node (ref "R49") (pin "1") (pinfunction "1_1") (pintype "passive"))
      (node (ref "U1") (pin "45") (pinfunction "PH4_45") (pintype "bidirectional"))
    )
    (net (code "81") (name "/I2C2_SDA") (class "Default")
      (node (ref "IC7") (pin "5") (pinfunction "SDA_5") (pintype "bidirectional"))
      (node (ref "R50") (pin "1") (pinfunction "1_1") (pintype "passive"))
      (node (ref "U1") (pin "46") (pinfunction "PH5_46") (pintype "bidirectional"))
    )
    (net (code "82") (name "/I2C3_SCL") (class "Default")
      (node (ref "R93") (pin "1") (pinfunction "1_1") (pintype "passive"))
      (node (ref "U1") (pin "119") (pinfunction "PA8_119") (pintype "bidirectional"))
    )
    (net (code "83") (name "/I2C3_SDA") (class "Default")
      (node (ref "R94") (pin "1") (pinfunction "1_1") (pintype "passive"))
      (node (ref "U1") (pin "85") (pinfunction "PH8_85") (pintype "bidirectional"))
    )
    (net (code "84") (name "/LED1") (class "Default")
      (node (ref "U1") (pin "86") (pinfunction "PH9_86") (pintype "bidirectional"))
    )
    (net (code "85") (name "/LED2") (class "Default")
      (node (ref "U1") (pin "87") (pinfunction "PH10_87") (pintype "bidirectional"))
    )
    (net (code "86") (name "/LED3") (class "Default")
      (node (ref "U1") (pin "88") (pinfunction "PH11_88") (pintype "bidirectional"))
    )
    (net (code "87") (name "/LED4") (class "Default")
      (node (ref "U1") (pin "11") (pinfunction "PI9_11") (pintype "bidirectional"))
    )
    (net (code "88") (name "/LED5") (class "Default")
      (node (ref "U1") (pin "12") (pinfunction "PI10_12") (pintype "bidirectional"))
    )
    (net (code "89") (name "/PMES1_O") (class "Default")
      (node (ref "U1") (pin "34") (pinfunction "PC2_34") (pintype "bidirectional"))
    )
    (net (code "90") (name "/PMES2_O") (class "Default")
      (node (ref "U1") (pin "35") (pinfunction "PC3_35") (pintype "bidirectional"))
    )
    (net (code "91") (name "/RST") (class "Default")
      (node (ref "D2") (pin "3") (pinfunction "I/O2_3") (pintype "bidirectional"))
      (node (ref "D4") (pin "1") (pinfunction "A_1") (pintype "passive"))
      (node (ref "P2") (pin "10") (pinfunction "10_10") (pintype "passive"))
      (node (ref "U1") (pin "31") (pinfunction "NRST_31") (pintype "bidirectional"))
    )
    (net (code "92") (name "/SDIO_CLK") (class "Default")
      (node (ref "U1") (pin "141") (pinfunction "PC12_141") (pintype "bidirectional"))
    )
    (net (code "93") (name "/SDIO_CMD") (class "Default")
      (node (ref "U1") (pin "144") (pinfunction "PD2_144") (pintype "bidirectional"))
    )
    (net (code "94") (name "/SDIO_D0") (class "Default")
      (node (ref "U1") (pin "117") (pinfunction "PC8_117") (pintype "bidirectional"))
    )
    (net (code "95") (name "/SDIO_D1") (class "Default")
      (node (ref "U1") (pin "118") (pinfunction "PC9_118") (pintype "bidirectional"))
    )
    (net (code "96") (name "/SDIO_D2") (class "Default")
      (node (ref "U1") (pin "139") (pinfunction "PC10_139") (pintype "bidirectional"))
    )
    (net (code "97") (name "/SDIO_D3") (class "Default")
      (node (ref "U1") (pin "140") (pinfunction "PC11_140") (pintype "bidirectional"))
    )
    (net (code "99") (name "/SPI5_MISO") (class "Default")
      (node (ref "U1") (pin "26") (pinfunction "PF8_26") (pintype "bidirectional"))
    )
    (net (code "100") (name "/SPI5_MOSI") (class "Default")
      (node (ref "U1") (pin "27") (pinfunction "PF9_27") (pintype "bidirectional"))
    )
    (net (code "101") (name "/SPI5_NSS") (class "Default")
      (node (ref "U1") (pin "24") (pinfunction "PF6_24") (pintype "bidirectional"))
    )
    (net (code "102") (name "/SPI5_SCK") (class "Default")
      (node (ref "U1") (pin "25") (pinfunction "PF7_25") (pintype "bidirectional"))
    )
    (net (code "103") (name "/SWCLK") (class "Default")
      (node (ref "D1") (pin "2") (pinfunction "I/O1_2") (pintype "bidirectional"))
      (node (ref "P2") (pin "4") (pinfunction "4_4") (pintype "passive"))
      (node (ref "U1") (pin "137") (pinfunction "PA14(JTCK-SWCLK)_137") (pintype "bidirectional"))
    )
    (net (code "104") (name "/SWDIO") (class "Default")
      (node (ref "D1") (pin "3") (pinfunction "I/O2_3") (pintype "bidirectional"))
      (node (ref "P2") (pin "2") (pinfunction "2_2") (pintype "passive"))
      (node (ref "U1") (pin "124") (pinfunction "PA13(JTMS-SWDIO)_124") (pintype "bidirectional"))
    )
    (net (code "105") (name "/TIM8_CH1") (class "Default")
      (node (ref "U1") (pin "115") (pinfunction "PC6_115") (pintype "bidirectional"))
    )
    (net (code "106") (name "/TIM8_CH2") (class "Default")
      (node (ref "U1") (pin "116") (pinfunction "PC7_116") (pintype "bidirectional"))
    )
    (net (code "107") (name "/TIM8_CH3") (class "Default")
      (node (ref "U1") (pin "176") (pinfunction "PI7_176") (pintype "bidirectional"))
    )
    (net (code "108") (name "/TIM8_CH4") (class "Default")
      (node (ref "U1") (pin "133") (pinfunction "PI2_133") (pintype "bidirectional"))
    )
    (net (code "109") (name "/USART1_RX") (class "Default")
      (node (ref "R43") (pin "1") (pinfunction "1_1") (pintype "passive"))
      (node (ref "U1") (pin "121") (pinfunction "PA10_121") (pintype "bidirectional"))
    )
    (net (code "110") (name "/USART1_TX") (class "Default")
      (node (ref "R62") (pin "2") (pinfunction "2_2") (pintype "passive"))
      (node (ref "U1") (pin "120") (pinfunction "PA9_120") (pintype "bidirectional"))
    )
    (net (code "111") (name "/USART2_RX") (class "Default")
      (node (ref "U1") (pin "47") (pinfunction "PA3_47") (pintype "bidirectional"))
    )
    (net (code "112") (name "/USART2_TX") (class "Default")
      (node (ref "U1") (pin "147") (pinfunction "PD5_147") (pintype "bidirectional"))
    )
    (net (code "113") (name "/USB_OTG_FS_N") (class "Default")
      (node (ref "R64") (pin "2") (pinfunction "2_2") (pintype "passive"))
      (node (ref "U1") (pin "122") (pinfunction "PA11_122") (pintype "bidirectional"))
    )
    (net (code "114") (name "/USB_OTG_FS_P") (class "Default")
      (node (ref "R63") (pin "1") (pinfunction "1_1") (pintype "passive"))
      (node (ref "U1") (pin "123") (pinfunction "PA12_123") (pintype "bidirectional"))
    )
    (net (code "115") (name "/U_DN") (class "Default")
      (node (ref "R64") (pin "1") (pinfunction "1_1") (pintype "passive"))
    )
    (net (code "116") (name "/U_DP") (class "Default")
      (node (ref "R63") (pin "2") (pinfunction "2_2") (pintype "passive"))
    )
    (net (code "117") (name "/U_RX") (class "Default")
      (node (ref "R62") (pin "1") (pinfunction "1_1") (pintype "passive"))
    )
    (net (code "118") (name "/U_TX") (class "Default")
      (node (ref "R43") (pin "2") (pinfunction "2_2") (pintype "passive"))
    )
    (net (code "119") (name "/VBAT") (class "Default")
      (node (ref "U1") (pin "6") (pinfunction "VBAT_6") (pintype "power_in+no_connect"))
    )
    (net (code "120") (name "/VREF") (class "Default")
      (node (ref "U1") (pin "38") (pinfunction "VREF+_38") (pintype "power_in+no_connect"))
    )
    (net (code "121") (name "GND") (class "Default")
      (node (ref "C1") (pin "1") (pinfunction "1_1") (pintype "passive"))
      (node (ref "C10") (pin "1") (pinfunction "1_1") (pintype "passive"))
      (node (ref "C11") (pin "1") (pinfunction "1_1") (pintype "passive"))
      (node (ref "C12") (pin "1") (pinfunction "1_1") (pintype "passive"))
      (node (ref "C13") (pin "1") (pinfunction "1_1") (pintype "passive"))
      (node (ref "C2") (pin "1") (pinfunction "1_1") (pintype "passive"))
      (node (ref "C3") (pin "1") (pinfunction "1_1") (pintype "passive"))
      (node (ref "C36") (pin "1") (pinfunction "1_1") (pintype "passive"))
      (node (ref "C37") (pin "1") (pinfunction "1_1") (pintype "passive"))
      (node (ref "C38") (pin "1") (pinfunction "1_1") (pintype "passive"))
      (node (ref "C39") (pin "1") (pinfunction "1_1") (pintype "passive"))
      (node (ref "C4") (pin "1") (pinfunction "1_1") (pintype "passive"))
      (node (ref "C40") (pin "1") (pinfunction "1_1") (pintype "passive"))
      (node (ref "C5") (pin "1") (pinfunction "1_1") (pintype "passive"))
      (node (ref "C52") (pin "1") (pinfunction "1_1") (pintype "passive"))
      (node (ref "C55") (pin "1") (pinfunction "1_1") (pintype "passive"))
      (node (ref "C56") (pin "1") (pinfunction "1_1") (pintype "passive"))
      (node (ref "C57") (pin "1") (pinfunction "1_1") (pintype "passive"))
      (node (ref "C58") (pin "1") (pinfunction "1_1") (pintype "passive"))
      (node (ref "C6") (pin "1") (pinfunction "1_1") (pintype "passive"))
      (node (ref "C7") (pin "1") (pinfunction "1_1") (pintype "passive"))
      (node (ref "C8") (pin "1") (pinfunction "1_1") (pintype "passive"))
      (node (ref "C9") (pin "1") (pinfunction "1_1") (pintype "passive"))
      (node (ref "D1") (pin "1") (pinfunction "GND_1") (pintype "power_in"))
      (node (ref "D2") (pin "1") (pinfunction "GND_1") (pintype "power_in"))
      (node (ref "IC3") (pin "1") (pinfunction "Vss_1") (pintype "power_in"))
      (node (ref "IC7") (pin "2") (pinfunction "A1_2") (pintype "input"))
      (node (ref "IC7") (pin "3") (pinfunction "A2_3") (pintype "input"))
      (node (ref "IC7") (pin "4") (pinfunction "GND_4") (pintype "power_in"))
      (node (ref "IC7") (pin "7") (pinfunction "WP_7") (pintype "input"))
      (node (ref "OSC1") (pin "2") (pinfunction "GND_2") (pintype "power_in"))
      (node (ref "P2") (pin "3") (pinfunction "3_3") (pintype "passive"))
      (node (ref "P2") (pin "5") (pinfunction "5_5") (pintype "passive"))
      (node (ref "P2") (pin "9") (pinfunction "9_9") (pintype "passive"))
      (node (ref "R95") (pin "1") (pinfunction "1_1") (pintype "passive"))
      (node (ref "U1") (pin "102") (pinfunction "VSS_102") (pintype "power_in"))
      (node (ref "U1") (pin "113") (pinfunction "VSS_113") (pintype "power_in"))
      (node (ref "U1") (pin "126") (pinfunction "VSS_126") (pintype "power_in"))
      (node (ref "U1") (pin "135") (pinfunction "VSS_135") (pintype "power_in"))
      (node (ref "U1") (pin "14") (pinfunction "VSS_14") (pintype "power_in"))
      (node (ref "U1") (pin "148") (pinfunction "VSS_148") (pintype "power_in"))
      (node (ref "U1") (pin "158") (pinfunction "VSS_158") (pintype "power_in"))
      (node (ref "U1") (pin "22") (pinfunction "VSS_22") (pintype "power_in"))
      (node (ref "U1") (pin "37") (pinfunction "VSSA_37") (pintype "power_in"))
      (node (ref "U1") (pin "48") (pinfunction "BYPASS_REG_48") (pintype "input"))
      (node (ref "U1") (pin "61") (pinfunction "VSS_61") (pintype "power_in"))
      (node (ref "U1") (pin "71") (pinfunction "VSS_71") (pintype "power_in"))
      (node (ref "U1") (pin "90") (pinfunction "VSS_90") (pintype "power_in"))
    )
    (net (code "122") (name "Net-(D4A-COMC)") (class "Default")
      (node (ref "D4") (pin "3") (pinfunction "COMC_3") (pintype "passive"))
      (node (ref "IC3") (pin "2") (pinfunction "~{RST}_2") (pintype "output"))
    )
    (net (code "123") (name "Net-(IC7-A0)") (class "Default")
      (node (ref "IC7") (pin "1") (pinfunction "A0_1") (pintype "input"))
      (node (ref "R95") (pin "2") (pinfunction "2_2") (pintype "passive"))
    )
    (net (code "124") (name "Net-(OSC1-OUT)") (class "Default")
      (node (ref "OSC1") (pin "3") (pinfunction "OUT_3") (pintype "output"))
      (node (ref "R105") (pin "1") (pinfunction "1_1") (pintype "passive"))
      (node (ref "R106") (pin "1") (pinfunction "1_1") (pintype "passive"))
    )
    (net (code "125") (name "Net-(Q2-OSC1)") (class "Default")
      (node (ref "C55") (pin "2") (pinfunction "2_2") (pintype "passive"))
      (node (ref "Q2") (pin "1") (pinfunction "OSC1_1") (pintype "passive"))
      (node (ref "U1") (pin "30") (pinfunction "PH1-OSC_OUT(PH1)_30") (pintype "bidirectional"))
    )
    (net (code "126") (name "Net-(Q2-OSC2)") (class "Default")
      (node (ref "C52") (pin "2") (pinfunction "2_2") (pintype "passive"))
      (node (ref "Q2") (pin "2") (pinfunction "OSC2_2") (pintype "passive"))
      (node (ref "U1") (pin "29") (pinfunction "PH0-OSC_IN(PH0)_29") (pintype "bidirectional"))
    )
    (net (code "127") (name "Net-(Q3-OSC1)") (class "Default")
      (node (ref "C36") (pin "2") (pinfunction "2_2") (pintype "passive"))
      (node (ref "Q3") (pin "1") (pinfunction "OSC1_1") (pintype "passive"))
      (node (ref "U1") (pin "9") (pinfunction "PC14-OSC32_IN(PC14)_9") (pintype "bidirectional"))
    )
    (net (code "128") (name "Net-(Q3-OSC2)") (class "Default")
      (node (ref "C37") (pin "2") (pinfunction "2_2") (pintype "passive"))
      (node (ref "Q3") (pin "2") (pinfunction "OSC2_2") (pintype "passive"))
      (node (ref "U1") (pin "10") (pinfunction "PC15-OSC32_OUT(PC15)_10") (pintype "bidirectional"))
    )
    (net (code "129") (name "Net-(U1B-PDR_ON)") (class "Default")
      (node (ref "R42") (pin "1") (pinfunction "1_1") (pintype "passive"))
      (node (ref "U1") (pin "171") (pinfunction "PDR_ON_171") (pintype "input"))
    )
    (net (code "130") (name "Net-(U1B-VCAP_1)") (class "Default")
      (node (ref "C57") (pin "2") (pinfunction "2_2") (pintype "passive"))
      (node (ref "U1") (pin "81") (pinfunction "VCAP_1_81") (pintype "power_in"))
    )
    (net (code "131") (name "Net-(U1B-VCAP_2)") (class "Default")
      (node (ref "C56") (pin "2") (pinfunction "2_2") (pintype "passive"))
      (node (ref "U1") (pin "125") (pinfunction "VCAP_2_125") (pintype "power_in"))
    )
    (net (code "132") (name "Net-(U1C-VDDA)") (class "Default")
      (node (ref "C13") (pin "2") (pinfunction "2_2") (pintype "passive"))
      (node (ref "L2") (pin "2") (pinfunction "2_2") (pintype "passive"))
      (node (ref "U1") (pin "39") (pinfunction "VDDA_39") (pintype "power_in"))
    )
    (net (code "133") (name "P3V3") (class "Default")
      (node (ref "C1") (pin "2") (pinfunction "2_2") (pintype "passive"))
      (node (ref "C10") (pin "2") (pinfunction "2_2") (pintype "passive"))
      (node (ref "C11") (pin "2") (pinfunction "2_2") (pintype "passive"))
      (node (ref "C12") (pin "2") (pinfunction "2_2") (pintype "passive"))
      (node (ref "C2") (pin "2") (pinfunction "2_2") (pintype "passive"))
      (node (ref "C3") (pin "2") (pinfunction "2_2") (pintype "passive"))
      (node (ref "C38") (pin "2") (pinfunction "2_2") (pintype "passive"))
      (node (ref "C39") (pin "2") (pinfunction "2_2") (pintype "passive"))
      (node (ref "C4") (pin "2") (pinfunction "2_2") (pintype "passive"))
      (node (ref "C40") (pin "2") (pinfunction "2_2") (pintype "passive"))
      (node (ref "C5") (pin "2") (pinfunction "2_2") (pintype "passive"))
      (node (ref "C58") (pin "2") (pinfunction "2_2") (pintype "passive"))
      (node (ref "C6") (pin "2") (pinfunction "2_2") (pintype "passive"))
      (node (ref "C7") (pin "2") (pinfunction "2_2") (pintype "passive"))
      (node (ref "C8") (pin "2") (pinfunction "2_2") (pintype "passive"))
      (node (ref "C9") (pin "2") (pinfunction "2_2") (pintype "passive"))
      (node (ref "D1") (pin "4") (pinfunction "VCC_4") (pintype "power_in"))
      (node (ref "D2") (pin "4") (pinfunction "VCC_4") (pintype "power_in"))
      (node (ref "IC3") (pin "3") (pinfunction "Vcc_3") (pintype "power_in"))
      (node (ref "IC7") (pin "8") (pinfunction "VCC_8") (pintype "power_in"))
      (node (ref "L2") (pin "1") (pinfunction "1_1") (pintype "passive"))
      (node (ref "OSC1") (pin "4") (pinfunction "VCC_4") (pintype "power_in"))
      (node (ref "P2") (pin "1") (pinfunction "1_1") (pintype "passive"))
      (node (ref "R42") (pin "2") (pinfunction "2_2") (pintype "passive"))
      (node (ref "R47") (pin "2") (pinfunction "2_2") (pintype "passive"))
      (node (ref "R48") (pin "2") (pinfunction "2_2") (pintype "passive"))
      (node (ref "R49") (pin "2") (pinfunction "2_2") (pintype "passive"))
      (node (ref "R50") (pin "2") (pinfunction "2_2") (pintype "passive"))
      (node (ref "R93") (pin "2") (pinfunction "2_2") (pintype "passive"))
      (node (ref "R94") (pin "2") (pinfunction "2_2") (pintype "passive"))
      (node (ref "U1") (pin "103") (pinfunction "VDD_103") (pintype "power_in"))
      (node (ref "U1") (pin "114") (pinfunction "VDD_114") (pintype "power_in"))
      (node (ref "U1") (pin "127") (pinfunction "VDD_127") (pintype "power_in"))
      (node (ref "U1") (pin "136") (pinfunction "VDD_136") (pintype "power_in"))
      (node (ref "U1") (pin "149") (pinfunction "VDD_149") (pintype "power_in"))
      (node (ref "U1") (pin "15") (pinfunction "VDD_15") (pintype "power_in"))
      (node (ref "U1") (pin "159") (pinfunction "VDD_159") (pintype "power_in"))
      (node (ref "U1") (pin "172") (pinfunction "VDD_172") (pintype "power_in"))
      (node (ref "U1") (pin "23") (pinfunction "VDD_23") (pintype "power_in"))
      (node (ref "U1") (pin "36") (pinfunction "VDD_36") (pintype "power_in"))
      (node (ref "U1") (pin "49") (pinfunction "VDD_49") (pintype "power_in"))
      (node (ref "U1") (pin "62") (pinfunction "VDD_62") (pintype "power_in"))
      (node (ref "U1") (pin "72") (pinfunction "VDD_72") (pintype "power_in"))
      (node (ref "U1") (pin "82") (pinfunction "VDD_82") (pintype "power_in"))
      (node (ref "U1") (pin "91") (pinfunction "VDD_91") (pintype "power_in"))
    )
    (net (code "134") (name "unconnected-(D2-I{slash}O1-Pad2)") (class "Default")
      (node (ref "D2") (pin "2") (pinfunction "I/O1_2") (pintype "bidirectional"))
    )
    (net (code "135") (name "unconnected-(OSC1-ST-Pad1)") (class "Default")
      (node (ref "OSC1") (pin "1") (pinfunction "ST_1") (pintype "input+no_connect"))
    )
    (net (code "136") (name "unconnected-(P2-Pad6)") (class "Default")
      (node (ref "P2") (pin "6") (pinfunction "6_6") (pintype "passive"))
    )
    (net (code "137") (name "unconnected-(P2-Pad7)") (class "Default")
      (node (ref "P2") (pin "7") (pinfunction "7_7") (pintype "passive+no_connect"))
    )
    (net (code "138") (name "unconnected-(P2-Pad8)") (class "Default")
      (node (ref "P2") (pin "8") (pinfunction "8_8") (pintype "passive+no_connect"))
    )
    (net (code "139") (name "unconnected-(U1A-PA0-WKUP(PA0)-Pad40)") (class "Default")
      (node (ref "U1") (pin "40") (pinfunction "PA0-WKUP(PA0)_40") (pintype "bidirectional"))
    )
    (net (code "140") (name "unconnected-(U1A-PA4-Pad50)") (class "Default")
      (node (ref "U1") (pin "50") (pinfunction "PA4_50") (pintype "bidirectional"))
    )
    (net (code "141") (name "unconnected-(U1A-PA5-Pad51)") (class "Default")
      (node (ref "U1") (pin "51") (pinfunction "PA5_51") (pintype "bidirectional"))
    )
    (net (code "142") (name "unconnected-(U1A-PA6-Pad52)") (class "Default")
      (node (ref "U1") (pin "52") (pinfunction "PA6_52") (pintype "bidirectional"))
    )
    (net (code "143") (name "unconnected-(U1A-PA15(JTDI)-Pad138)") (class "Default")
      (node (ref "U1") (pin "138") (pinfunction "PA15(JTDI)_138") (pintype "bidirectional"))
    )
    (net (code "144") (name "unconnected-(U1A-PB1-Pad57)") (class "Default")
      (node (ref "U1") (pin "57") (pinfunction "PB1_57") (pintype "bidirectional"))
    )
    (net (code "145") (name "unconnected-(U1A-PB3(JTDO{slash}TRACESWO)-Pad161)") (class "Default")
      (node (ref "U1") (pin "161") (pinfunction "PB3(JTDO/TRACESWO)_161") (pintype "bidirectional"))
    )
    (net (code "146") (name "unconnected-(U1A-PB4(NJTRST)-Pad162)") (class "Default")
      (node (ref "U1") (pin "162") (pinfunction "PB4(NJTRST)_162") (pintype "bidirectional"))
    )
    (net (code "147") (name "unconnected-(U1A-PB5-Pad163)") (class "Default")
      (node (ref "U1") (pin "163") (pinfunction "PB5_163") (pintype "bidirectional"))
    )
    (net (code "148") (name "unconnected-(U1A-PB8-Pad167)") (class "Default")
      (node (ref "U1") (pin "167") (pinfunction "PB8_167") (pintype "bidirectional"))
    )
    (net (code "149") (name "unconnected-(U1A-PB9-Pad168)") (class "Default")
      (node (ref "U1") (pin "168") (pinfunction "PB9_168") (pintype "bidirectional"))
    )
    (net (code "150") (name "unconnected-(U1A-PC13-Pad8)") (class "Default")
      (node (ref "U1") (pin "8") (pinfunction "PC13_8") (pintype "bidirectional"))
    )
    (net (code "151") (name "unconnected-(U1A-PD3-Pad145)") (class "Default")
      (node (ref "U1") (pin "145") (pinfunction "PD3_145") (pintype "bidirectional"))
    )
    (net (code "152") (name "unconnected-(U1A-PD4-Pad146)") (class "Default")
      (node (ref "U1") (pin "146") (pinfunction "PD4_146") (pintype "bidirectional"))
    )
    (net (code "153") (name "unconnected-(U1A-PD6-Pad150)") (class "Default")
      (node (ref "U1") (pin "150") (pinfunction "PD6_150") (pintype "bidirectional"))
    )
    (net (code "154") (name "unconnected-(U1A-PD7-Pad151)") (class "Default")
      (node (ref "U1") (pin "151") (pinfunction "PD7_151") (pintype "bidirectional"))
    )
    (net (code "155") (name "unconnected-(U1A-PE2-Pad1)") (class "Default")
      (node (ref "U1") (pin "1") (pinfunction "PE2_1") (pintype "bidirectional"))
    )
    (net (code "156") (name "unconnected-(U1A-PF10-Pad28)") (class "Default")
      (node (ref "U1") (pin "28") (pinfunction "PF10_28") (pintype "bidirectional"))
    )
    (net (code "157") (name "unconnected-(U1B-PG3-Pad107)") (class "Default")
      (node (ref "U1") (pin "107") (pinfunction "PG3_107") (pintype "bidirectional"))
    )
    (net (code "158") (name "unconnected-(U1B-PG9-Pad152)") (class "Default")
      (node (ref "U1") (pin "152") (pinfunction "PG9_152") (pintype "bidirectional"))
    )
    (net (code "159") (name "unconnected-(U1B-PG10-Pad153)") (class "Default")
      (node (ref "U1") (pin "153") (pinfunction "PG10_153") (pintype "bidirectional"))
    )
    (net (code "160") (name "unconnected-(U1B-PG12-Pad155)") (class "Default")
      (node (ref "U1") (pin "155") (pinfunction "PG12_155") (pintype "bidirectional"))
    )
    (net (code "161") (name "unconnected-(U1B-PG13-Pad156)") (class "Default")
      (node (ref "U1") (pin "156") (pinfunction "PG13_156") (pintype "bidirectional"))
    )
    (net (code "162") (name "unconnected-(U1B-PG14-Pad157)") (class "Default")
      (node (ref "U1") (pin "157") (pinfunction "PG14_157") (pintype "bidirectional"))
    )
    (net (code "163") (name "unconnected-(U1B-PH2-Pad43)") (class "Default")
      (node (ref "U1") (pin "43") (pinfunction "PH2_43") (pintype "bidirectional"))
    )
    (net (code "164") (name "unconnected-(U1B-PH12-Pad89)") (class "Default")
      (node (ref "U1") (pin "89") (pinfunction "PH12_89") (pintype "bidirectional+no_connect"))
    )
    (net (code "165") (name "unconnected-(U1B-PI0-Pad131)") (class "Default")
      (node (ref "U1") (pin "131") (pinfunction "PI0_131") (pintype "bidirectional"))
    )
    (net (code "166") (name "unconnected-(U1B-PI1-Pad132)") (class "Default")
      (node (ref "U1") (pin "132") (pinfunction "PI1_132") (pintype "bidirectional"))
    )
    (net (code "167") (name "unconnected-(U1B-PI8-Pad7)") (class "Default")
      (node (ref "U1") (pin "7") (pinfunction "PI8_7") (pintype "bidirectional"))
    )
    (net (code "168") (name "unconnected-(U1B-PI11-Pad13)") (class "Default")
      (node (ref "U1") (pin "13") (pinfunction "PI11_13") (pintype "bidirectional"))
    )
  )
)
